# LDO.net
KiCad netlist of a schematic drawn in Altium Designer
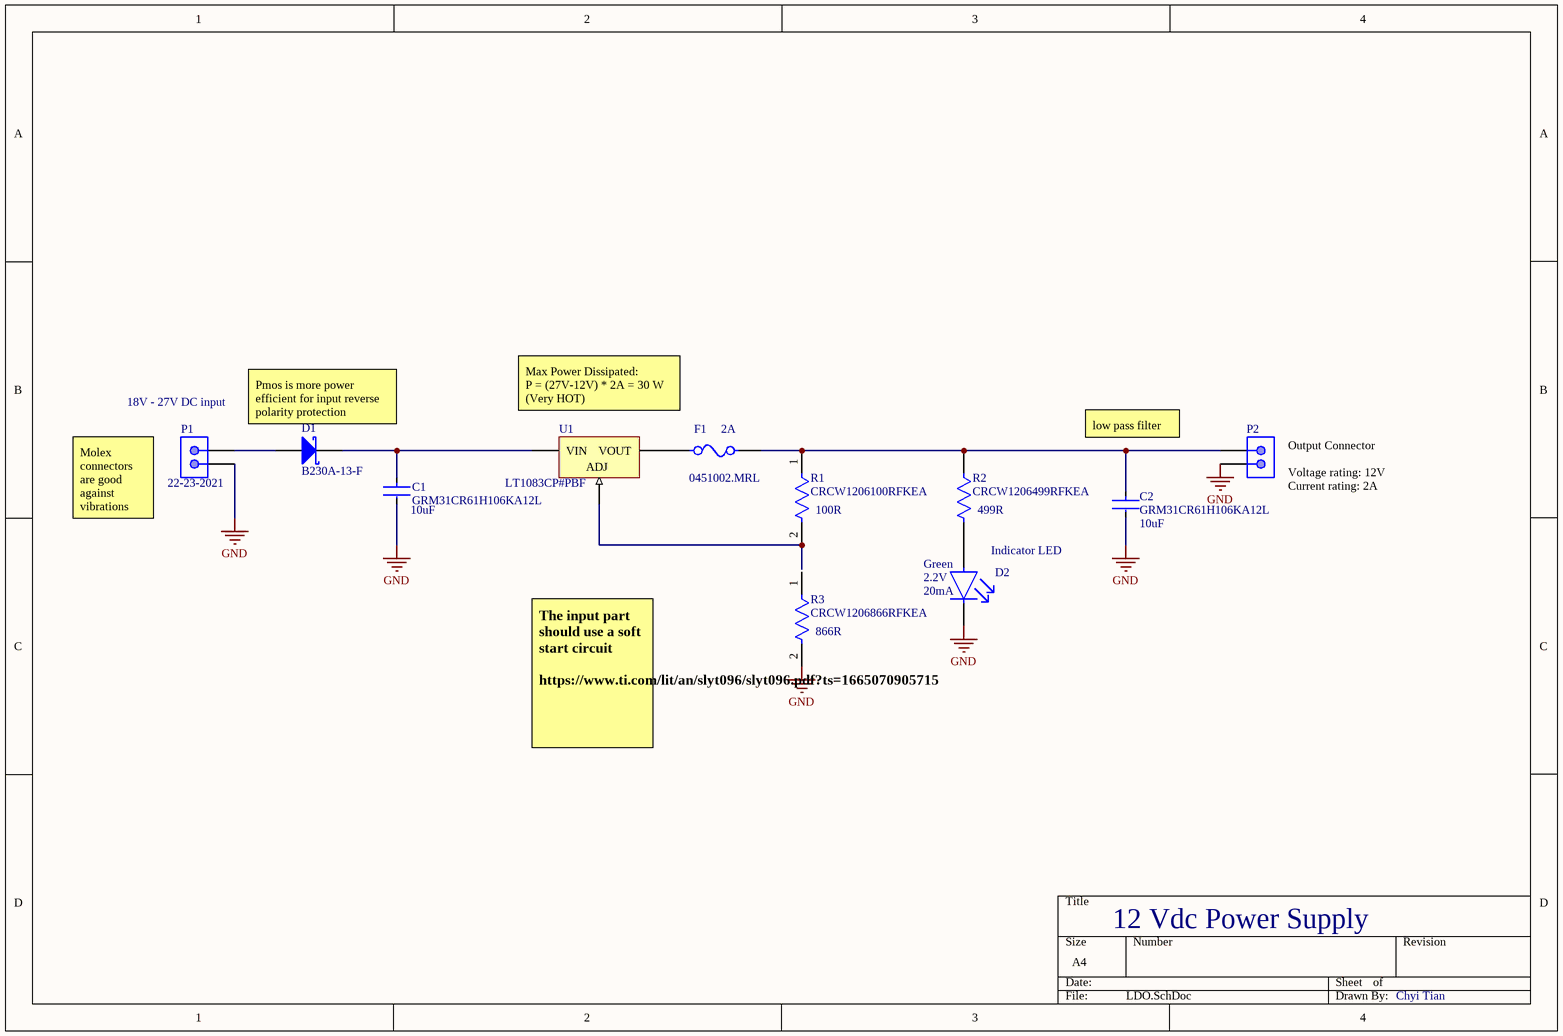
[diagram p0: LDO.SchDoc]

(export (version "E")
  (design (tool "Eeschema 10.0.6"))
  (components
    (comp (ref "C1")
      (value "GRM31CR61H106KA12L")
      (footprint "FP-GRM31-0_2-MFG")
      (description "CAP CER 10UF 50V X5R 1206")
      (fields
        (field (name "OCTOPART") "https://octopart.com/grm31cr61h106ka12l-murata-18903335")
        (field (name "TOLERANCE") "10%")
        (field (name "CAPACITANCE") "10uF")
      )
      (libsource (lib "Altium Content Vault") (part "11868f565c42a9108669ba33697ecf6"))
    )
    (comp (ref "C2")
      (value "GRM31CR61H106KA12L")
      (footprint "FP-GRM31-0_2-MFG")
      (description "CAP CER 10UF 50V X5R 1206")
      (fields
        (field (name "OCTOPART") "https://octopart.com/grm31cr61h106ka12l-murata-18903335")
        (field (name "TOLERANCE") "10%")
        (field (name "CAPACITANCE") "10uF")
      )
      (libsource (lib "Altium Content Vault") (part "11868f565c42a9108669ba33697ecf6"))
    )
    (comp (ref "D1")
      (value "B230A-13-F")
      (footprint "DIOD-SMA-2_V")
      (fields (field (name "MANUFACTURER") "Diodes Inc"))
      (libsource (lib "Altium Content Vault") (part "DIOD-DSKY-A1K2-2"))
    )
    (comp (ref "D2")
      (value "597-3301-507F")
      (footprint "FP-597-3301-507F-MFG")
      (description "LED GREEN CLEAR 1208 SMD")
      (fields
        (field (name "OCTOPART") "https://octopart.com/597-3301-507f-dialight-117926")
        (field (name "MANUFACTURER") "Dialight")
        (field (name "FORWARD CURRENT") "20mA")
        (field (name "FORWARD VOLTAGE") "2.2V")
        (field (name "COLOUR") "Green")
      )
      (libsource (lib "Altium Content Vault") (part "8706943c75ba83719d021d2fdc84c58"))
    )
    (comp (ref "F1")
      (value "0451002.MRL")
      (footprint "FP-0451-MFG")
      (description "FUSE BOARD MNT 2A 125VAC/VDC SMD")
      (fields
        (field (name "MANUFACTURER") "Littelfuse")
        (field (name "FUSE CURRENT") "2A")
        (field (name "OCTOPART") "https://octopart.com/0451002.mrl-littelfuse-566376")
      )
      (libsource (lib "Altium Content Vault") (part "5bcf9b9f640e542cf0359d10258e979"))
    )
    (comp (ref "P1")
      (value "22-23-2021")
      (footprint "MOLX-22-23-2021_V")
      (libsource (lib "") (part "CN-1P-M-R2_1"))
    )
    (comp (ref "P2")
      (value "22-23-2021")
      (footprint "MOLX-22-23-2021_V")
      (libsource (lib "Altium Content Vault") (part "CN-1P-M-R2"))
    )
    (comp (ref "R1")
      (value "CRCW1206100RFKEA")
      (footprint "FP-CRCW1206-e3-MFG")
      (description "RES Thick Film, 100Ω, 1%, 0.25W, 100ppm/°C, 1206")
      (fields (field (name "RESISTANCE") "100R") (field (name "TOLERANCE") "1%"))
      (libsource (lib "Altium Content Vault") (part "1029c3af85768c4190bb7ad29bc67b5"))
    )
    (comp (ref "R2")
      (value "CRCW1206499RFKEA")
      (footprint "FP-CRCW1206-e3-IPC_B")
      (description "RES Thick Film, 499Ω, 1%, 0.25W, 100ppm/°C, 1206")
      (fields (field (name "RESISTANCE") "499R") (field (name "TOLERANCE") "1%"))
      (libsource (lib "") (part "1029c3af85768c4190bb7ad29bc67b5_1"))
    )
    (comp (ref "R3")
      (value "CRCW1206866RFKEA")
      (footprint "FP-CRCW1206-e3-MFG")
      (description "RES Thick Film, 866Ω, 1%, 0.25W, 100ppm/°C, 1206")
      (fields (field (name "TOLERANCE") "1%") (field (name "RESISTANCE") "866R"))
      (libsource (lib "Altium Content Vault") (part "1029c3af85768c4190bb7ad29bc67b5"))
    )
    (comp (ref "U1")
      (value "LT1083CP#PBF")
      (footprint "LT-P-3-S-TO-247")
      (fields (field (name "MANUFACTURER") "Linear Technology"))
      (libsource (lib "Altium Content Vault") (part "LT-LT1XXXX"))
    )
  )
  (nets
    (net (code "1") (name "GND") (class "Default")
      (node (ref "C1") (pin "2") (pinfunction "2_2") (pintype "passive"))
      (node (ref "C2") (pin "2") (pinfunction "2_2") (pintype "passive"))
      (node (ref "D2") (pin "1") (pinfunction "C_1") (pintype "passive"))
      (node (ref "P1") (pin "1") (pinfunction "1_1") (pintype "passive"))
      (node (ref "P2") (pin "2") (pinfunction "2_2") (pintype "passive"))
      (node (ref "R3") (pin "2") (pinfunction "2_2") (pintype "passive"))
    )
    (net (code "2") (name "Net-(C2-Pad1)") (class "Default")
      (node (ref "C2") (pin "1") (pinfunction "1_1") (pintype "passive"))
      (node (ref "F1") (pin "2") (pinfunction "2_2") (pintype "passive"))
      (node (ref "P2") (pin "1") (pinfunction "1_1") (pintype "passive"))
      (node (ref "R1") (pin "1") (pinfunction "1_1") (pintype "passive"))
      (node (ref "R2") (pin "1") (pinfunction "1_1") (pintype "passive"))
    )
    (net (code "3") (name "Net-(D1-A)") (class "Default")
      (node (ref "D1") (pin "1") (pinfunction "A_1") (pintype "passive"))
      (node (ref "P1") (pin "2") (pinfunction "2_2") (pintype "passive"))
    )
    (net (code "4") (name "Net-(D1-K)") (class "Default")
      (node (ref "C1") (pin "1") (pinfunction "1_1") (pintype "passive"))
      (node (ref "D1") (pin "2") (pinfunction "K_2") (pintype "passive"))
      (node (ref "U1") (pin "3") (pinfunction "VIN_3") (pintype "power_in"))
    )
    (net (code "5") (name "Net-(D2-A)") (class "Default")
      (node (ref "D2") (pin "2") (pinfunction "A_2") (pintype "passive"))
      (node (ref "R2") (pin "2") (pinfunction "2_2") (pintype "passive"))
    )
    (net (code "6") (name "Net-(U1-ADJ)") (class "Default")
      (node (ref "R1") (pin "2") (pinfunction "2_2") (pintype "passive"))
      (node (ref "U1") (pin "1") (pinfunction "ADJ_1") (pintype "input"))
    )
    (net (code "7") (name "Net-(U1-VOUT)") (class "Default")
      (node (ref "F1") (pin "1") (pinfunction "1_1") (pintype "passive"))
      (node (ref "U1") (pin "2") (pinfunction "VOUT_2") (pintype "power_in"))
    )
    (net (code "8") (name "unconnected-(R3-Pad1)") (class "Default")
      (node (ref "R3") (pin "1") (pinfunction "1_1") (pintype "passive"))
    )
  )
)
